# simplePDwithBatteryv1.net
KiCad netlist of a schematic drawn in EAGLE
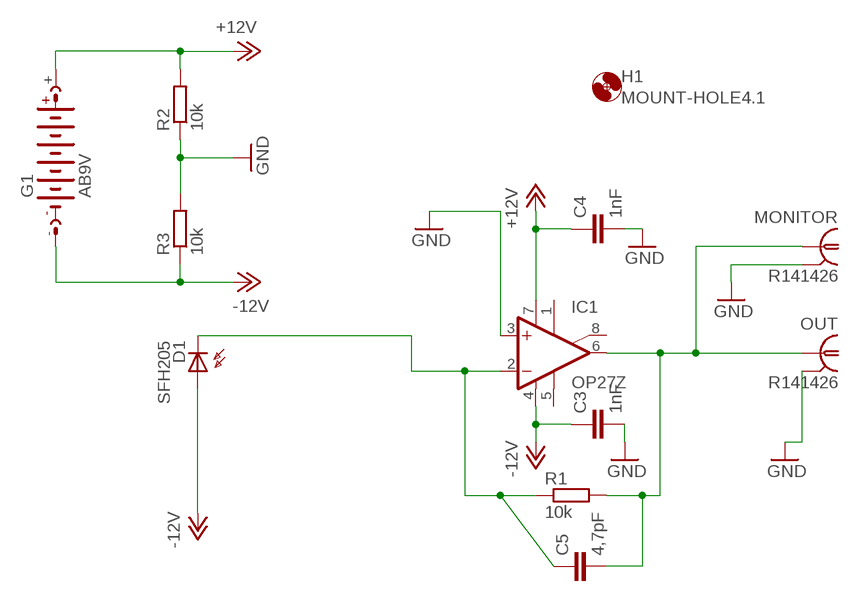
[diagram p0: schematic, sheet 1]

(export (version "E")
  (design (tool "Eeschema 10.0.6"))
  (components
    (comp (ref "C3")
      (value "1nF")
      (footprint "eagle-import:C025-050X050")
      (libsource (lib "eagle-import") (part "C-EU025-050X050"))
    )
    (comp (ref "C4")
      (value "1nF")
      (footprint "eagle-import:C025-050X050")
      (libsource (lib "eagle-import") (part "C-EU025-050X050"))
    )
    (comp (ref "C5")
      (value "4,7pF")
      (footprint "eagle-import:C025-050X050")
      (libsource (lib "eagle-import") (part "C-EU025-050X050"))
    )
    (comp (ref "D1")
      (value "SFH205")
      (footprint "eagle-import:SFH205")
      (libsource (lib "eagle-import") (part "SFH205"))
    )
    (comp (ref "G1")
      (value "AB9V")
      (footprint "eagle-import:AB9V")
      (libsource (lib "eagle-import") (part "AB9V"))
    )
    (comp (ref "H1")
      (value "MOUNT-HOLE4.1")
      (footprint "eagle-import:4,1")
      (libsource (lib "eagle-import") (part "MOUNT-HOLE4.1"))
    )
    (comp (ref "IC1")
      (value "OP27Z")
      (footprint "eagle-import:DIL08")
      (libsource (lib "eagle-import") (part "OP27Z"))
    )
    (comp (ref "MONITOR")
      (value "R141426")
      (footprint "eagle-import:R141426")
      (fields (field (name "MF") "FARNELL") (field (name "MPN") "R141426161"))
      (libsource (lib "eagle-import") (part "R141426"))
    )
    (comp (ref "OUT")
      (value "R141426")
      (footprint "eagle-import:R141426")
      (fields (field (name "MF") "FARNELL") (field (name "MPN") "R141426161"))
      (libsource (lib "eagle-import") (part "R141426"))
    )
    (comp (ref "R1")
      (value "10k")
      (footprint "eagle-import:0207_5V")
      (libsource (lib "eagle-import") (part "R-EU_0207/5V"))
    )
    (comp (ref "R2")
      (value "10k")
      (footprint "eagle-import:0204_5")
      (libsource (lib "eagle-import") (part "R-EU_0204/5"))
    )
    (comp (ref "R3")
      (value "10k")
      (footprint "eagle-import:0204_5")
      (libsource (lib "eagle-import") (part "R-EU_0204/5"))
    )
  )
  (nets
    (net (code "1") (name "+12V") (class "Default")
      (node (ref "C4") (pin "1") (pinfunction "1_1") (pintype "passive"))
      (node (ref "G1") (pin "+") (pinfunction "+_+") (pintype "passive"))
      (node (ref "IC1") (pin "7") (pinfunction "V+_7") (pintype "power_in"))
      (node (ref "R2") (pin "2") (pinfunction "2_2") (pintype "passive"))
    )
    (net (code "2") (name "-12V") (class "Default")
      (node (ref "C3") (pin "1") (pinfunction "1_1") (pintype "passive"))
      (node (ref "D1") (pin "A") (pinfunction "A_A") (pintype "passive"))
      (node (ref "G1") (pin "-") (pinfunction "-_-") (pintype "passive"))
      (node (ref "IC1") (pin "4") (pinfunction "V-_4") (pintype "power_in"))
      (node (ref "R3") (pin "1") (pinfunction "1_1") (pintype "passive"))
    )
    (net (code "3") (name "GND") (class "Default")
      (node (ref "C3") (pin "2") (pinfunction "2_2") (pintype "passive"))
      (node (ref "C4") (pin "2") (pinfunction "2_2") (pintype "passive"))
      (node (ref "IC1") (pin "3") (pinfunction "+IN_3") (pintype "input"))
      (node (ref "MONITOR") (pin "2") (pinfunction "2_2") (pintype "passive"))
      (node (ref "MONITOR") (pin "3") (pinfunction "2_3") (pintype "passive"))
      (node (ref "MONITOR") (pin "4") (pinfunction "2_4") (pintype "passive"))
      (node (ref "MONITOR") (pin "5") (pinfunction "2_5") (pintype "passive"))
      (node (ref "OUT") (pin "2") (pinfunction "2_2") (pintype "passive"))
      (node (ref "OUT") (pin "3") (pinfunction "2_3") (pintype "passive"))
      (node (ref "OUT") (pin "4") (pinfunction "2_4") (pintype "passive"))
      (node (ref "OUT") (pin "5") (pinfunction "2_5") (pintype "passive"))
      (node (ref "R2") (pin "1") (pinfunction "1_1") (pintype "passive"))
      (node (ref "R3") (pin "2") (pinfunction "2_2") (pintype "passive"))
    )
    (net (code "4") (name "Net-(D1-C)") (class "Default")
      (node (ref "C5") (pin "1") (pinfunction "1_1") (pintype "passive"))
      (node (ref "D1") (pin "K") (pinfunction "C_K") (pintype "passive"))
      (node (ref "IC1") (pin "2") (pinfunction "-IN_2") (pintype "input"))
      (node (ref "R1") (pin "1") (pinfunction "1_1") (pintype "passive"))
    )
    (net (code "5") (name "Net-(IC1-OUT)") (class "Default")
      (node (ref "C5") (pin "2") (pinfunction "2_2") (pintype "passive"))
      (node (ref "IC1") (pin "6") (pinfunction "OUT_6") (pintype "output"))
      (node (ref "MONITOR") (pin "1") (pinfunction "1_1") (pintype "passive"))
      (node (ref "OUT") (pin "1") (pinfunction "1_1") (pintype "passive"))
      (node (ref "R1") (pin "2") (pinfunction "2_2") (pintype "passive"))
    )
    (net (code "6") (name "unconnected-(IC1-ON1-Pad1)") (class "Default")
      (node (ref "IC1") (pin "1") (pinfunction "ON1_1") (pintype "passive"))
    )
    (net (code "7") (name "unconnected-(IC1-ON2-Pad8)") (class "Default")
      (node (ref "IC1") (pin "8") (pinfunction "ON2_8") (pintype "passive"))
    )
    (net (code "8") (name "unconnected-(IC1-OPT-Pad5)") (class "Default")
      (node (ref "IC1") (pin "5") (pinfunction "OPT_5") (pintype "passive"))
    )
  )
)
